# Twintig-IMUs.net
KiCad netlist of a schematic drawn in Altium Designer
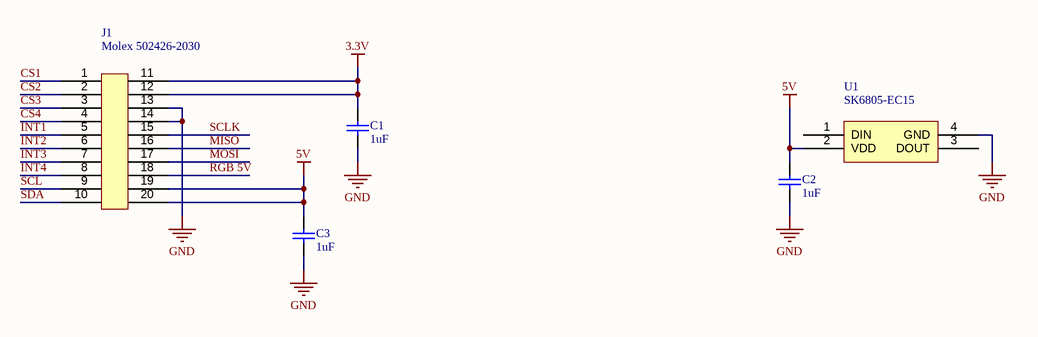
[diagram p0: Twintig-IMUs.SchDoc]

(export (version "E")
  (design (tool "Eeschema 10.0.6"))
  (components
    (comp (ref "C1") (value "1uF") (footprint "Capacitor 0402") (libsource (lib "x-io") (part "Capacitor")))
    (comp (ref "C2") (value "1uF") (footprint "Capacitor 0402") (libsource (lib "x-io") (part "Capacitor")))
    (comp (ref "C3") (value "1uF") (footprint "Capacitor 0402") (libsource (lib "x-io") (part "Capacitor")))
    (comp (ref "J1")
      (value "Molex 502426-2030")
      (footprint "Molex 502426-2030")
      (libsource (lib "x-io") (part "Molex 502426-2030"))
    )
    (comp (ref "U1")
      (value "SK6805-EC15")
      (footprint "SK6805-EC15")
      (libsource (lib "x-io") (part "SK6805-EC15"))
    )
  )
  (nets
    (net (code "1") (name "/CS1") (class "Default")
      (node (ref "J1") (pin "1") (pinfunction "1_1") (pintype "passive"))
    )
    (net (code "2") (name "/CS2") (class "Default")
      (node (ref "J1") (pin "2") (pinfunction "2_2") (pintype "passive"))
    )
    (net (code "3") (name "/CS3") (class "Default")
      (node (ref "J1") (pin "3") (pinfunction "3_3") (pintype "passive"))
    )
    (net (code "4") (name "/CS4") (class "Default")
      (node (ref "J1") (pin "4") (pinfunction "4_4") (pintype "passive"))
    )
    (net (code "5") (name "/INT1") (class "Default")
      (node (ref "J1") (pin "5") (pinfunction "5_5") (pintype "passive"))
    )
    (net (code "6") (name "/INT2") (class "Default")
      (node (ref "J1") (pin "6") (pinfunction "6_6") (pintype "passive"))
    )
    (net (code "7") (name "/INT3") (class "Default")
      (node (ref "J1") (pin "7") (pinfunction "7_7") (pintype "passive"))
    )
    (net (code "8") (name "/INT4") (class "Default")
      (node (ref "J1") (pin "8") (pinfunction "8_8") (pintype "passive"))
    )
    (net (code "9") (name "/MISO") (class "Default")
      (node (ref "J1") (pin "16") (pinfunction "16_16") (pintype "passive"))
    )
    (net (code "10") (name "/MOSI") (class "Default")
      (node (ref "J1") (pin "17") (pinfunction "17_17") (pintype "passive"))
    )
    (net (code "11") (name "/RGB 5V") (class "Default")
      (node (ref "J1") (pin "18") (pinfunction "18_18") (pintype "passive"))
    )
    (net (code "12") (name "/SCL") (class "Default")
      (node (ref "J1") (pin "9") (pinfunction "9_9") (pintype "passive"))
    )
    (net (code "13") (name "/SCLK") (class "Default")
      (node (ref "J1") (pin "15") (pinfunction "15_15") (pintype "passive"))
    )
    (net (code "14") (name "/SDA") (class "Default")
      (node (ref "J1") (pin "10") (pinfunction "10_10") (pintype "passive"))
    )
    (net (code "15") (name "3.3V") (class "Default")
      (node (ref "C1") (pin "2") (pinfunction "2_2") (pintype "passive"))
      (node (ref "J1") (pin "11") (pinfunction "11_11") (pintype "passive"))
      (node (ref "J1") (pin "12") (pinfunction "12_12") (pintype "passive"))
    )
    (net (code "16") (name "5V") (class "Default")
      (node (ref "C2") (pin "2") (pinfunction "2_2") (pintype "passive"))
      (node (ref "C3") (pin "2") (pinfunction "2_2") (pintype "passive"))
      (node (ref "J1") (pin "19") (pinfunction "19_19") (pintype "passive"))
      (node (ref "J1") (pin "20") (pinfunction "20_20") (pintype "passive"))
      (node (ref "U1") (pin "2") (pinfunction "VDD_2") (pintype "passive"))
    )
    (net (code "17") (name "GND") (class "Default")
      (node (ref "C1") (pin "1") (pinfunction "1_1") (pintype "passive"))
      (node (ref "C2") (pin "1") (pinfunction "1_1") (pintype "passive"))
      (node (ref "C3") (pin "1") (pinfunction "1_1") (pintype "passive"))
      (node (ref "J1") (pin "13") (pinfunction "13_13") (pintype "passive"))
      (node (ref "J1") (pin "14") (pinfunction "14_14") (pintype "passive"))
      (node (ref "U1") (pin "4") (pinfunction "GND_4") (pintype "passive"))
    )
    (net (code "18") (name "unconnected-(U1-DIN-Pad1)") (class "Default")
      (node (ref "U1") (pin "1") (pinfunction "DIN_1") (pintype "passive"))
    )
    (net (code "19") (name "unconnected-(U1-DOUT-Pad3)") (class "Default")
      (node (ref "U1") (pin "3") (pinfunction "DOUT_3") (pintype "passive"))
    )
  )
)
